# ERN_Main_2.net
KiCad netlist of a schematic drawn in Altium Designer
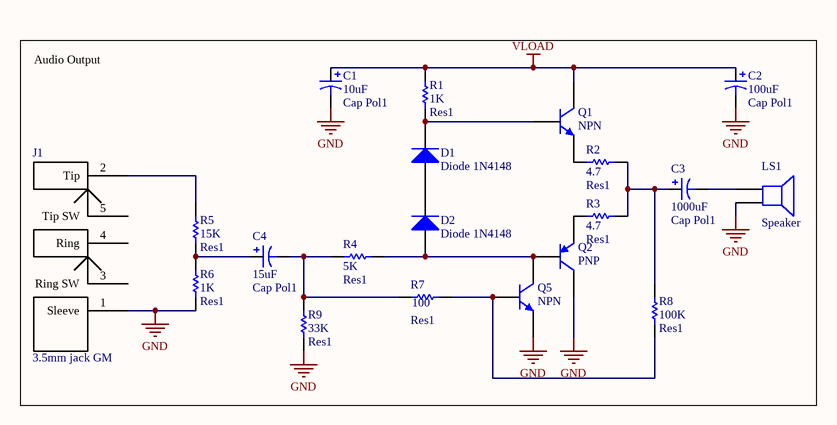
[diagram p0: ERN_Main_2.SchDoc]

(export (version "E")
  (design (tool "Eeschema 10.0.6"))
  (components
    (comp (ref "C1")
      (value "Cap Pol1")
      (footprint "Cap_10uF")
      (description "Polarized Capacitor (Radial)")
      (fields (field (name "ALTIUM_VALUE") "10uF") (field (name "PUBLISHER") "Altium Limited"))
      (libsource (lib "Miscellaneous Devices") (part "Cap Pol1"))
    )
    (comp (ref "C2")
      (value "Cap Pol1")
      (footprint "Cap_47uF_100uF")
      (description "Polarized Capacitor (Radial)")
      (fields (field (name "ALTIUM_VALUE") "100uF") (field (name "PUBLISHER") "Altium Limited"))
      (libsource (lib "Miscellaneous Devices") (part "Cap Pol1"))
    )
    (comp (ref "C3")
      (value "Cap Pol1")
      (footprint "Cap_1000uF")
      (description "Polarized Capacitor (Radial)")
      (fields (field (name "ALTIUM_VALUE") "1000uF") (field (name "PUBLISHER") "Altium Limited"))
      (libsource (lib "Miscellaneous Devices") (part "Cap Pol1"))
    )
    (comp (ref "C4")
      (value "Cap Pol1")
      (footprint "Cap_10uF")
      (description "Polarized Capacitor (Radial)")
      (fields (field (name "ALTIUM_VALUE") "15uF") (field (name "PUBLISHER") "Altium Limited"))
      (libsource (lib "Miscellaneous Devices") (part "Cap Pol1"))
    )
    (comp (ref "D1")
      (value "Diode 1N4148")
      (footprint "DO-35")
      (description "High Conductance Fast Diode")
      (fields (field (name "PUBLISHER") "Altium Limited"))
      (libsource (lib "Miscellaneous Devices") (part "Diode 1N4148"))
    )
    (comp (ref "D2")
      (value "Diode 1N4148")
      (footprint "DO-35")
      (description "High Conductance Fast Diode")
      (fields (field (name "PUBLISHER") "Altium Limited"))
      (libsource (lib "Miscellaneous Devices") (part "Diode 1N4148"))
    )
    (comp (ref "J1")
      (value "3.5mm jack GM")
      (footprint "3.5mm jack GM")
      (libsource (lib "ECE Lib 22") (part "3.5mm jack GM"))
    )
    (comp (ref "LS1")
      (value "Speaker")
      (footprint "PIN2")
      (description "Loudspeaker")
      (fields (field (name "PUBLISHER") "Altium Limited"))
      (libsource (lib "Miscellaneous Devices") (part "Speaker"))
    )
    (comp (ref "Q1")
      (value "NPN")
      (footprint "TO92254P460H750-3")
      (description "NPN Bipolar Transistor")
      (fields (field (name "PUBLISHER") "Altium Limited"))
      (libsource (lib "Miscellaneous Devices") (part "NPN"))
    )
    (comp (ref "Q2")
      (value "PNP")
      (footprint "TO92254P460H750-3")
      (description "PNP Bipolar Transistor")
      (fields (field (name "PUBLISHER") "Altium Limited"))
      (libsource (lib "Miscellaneous Devices") (part "PNP"))
    )
    (comp (ref "Q5")
      (value "NPN")
      (footprint "TO92254P460H750-3")
      (description "NPN Bipolar Transistor")
      (fields (field (name "PUBLISHER") "Altium Limited"))
      (libsource (lib "Miscellaneous Devices") (part "NPN"))
    )
    (comp (ref "R1")
      (value "Res1")
      (footprint "AXIAL-0.3")
      (description "Resistor")
      (fields (field (name "ALTIUM_VALUE") "1K") (field (name "PUBLISHER") "Altium Limited"))
      (libsource (lib "Miscellaneous Devices") (part "Res1"))
    )
    (comp (ref "R2")
      (value "Res1")
      (footprint "AXIAL-0.3")
      (description "Resistor")
      (fields (field (name "ALTIUM_VALUE") "4.7") (field (name "PUBLISHER") "Altium Limited"))
      (libsource (lib "Miscellaneous Devices") (part "Res1"))
    )
    (comp (ref "R3")
      (value "Res1")
      (footprint "AXIAL-0.3")
      (description "Resistor")
      (fields (field (name "ALTIUM_VALUE") "4.7") (field (name "PUBLISHER") "Altium Limited"))
      (libsource (lib "Miscellaneous Devices") (part "Res1"))
    )
    (comp (ref "R4")
      (value "Res1")
      (footprint "AXIAL-0.3")
      (description "Resistor")
      (fields (field (name "ALTIUM_VALUE") "5K") (field (name "PUBLISHER") "Altium Limited"))
      (libsource (lib "Miscellaneous Devices") (part "Res1"))
    )
    (comp (ref "R5")
      (value "Res1")
      (footprint "AXIAL-0.3")
      (description "Resistor")
      (fields (field (name "ALTIUM_VALUE") "15K") (field (name "PUBLISHER") "Altium Limited"))
      (libsource (lib "Miscellaneous Devices") (part "Res1"))
    )
    (comp (ref "R6")
      (value "Res1")
      (footprint "AXIAL-0.3")
      (description "Resistor")
      (fields (field (name "ALTIUM_VALUE") "1K") (field (name "PUBLISHER") "Altium Limited"))
      (libsource (lib "Miscellaneous Devices") (part "Res1"))
    )
    (comp (ref "R7")
      (value "Res1")
      (footprint "AXIAL-0.3")
      (description "Resistor")
      (fields (field (name "ALTIUM_VALUE") "100") (field (name "PUBLISHER") "Altium Limited"))
      (libsource (lib "Miscellaneous Devices") (part "Res1"))
    )
    (comp (ref "R8")
      (value "Res1")
      (footprint "AXIAL-0.3")
      (description "Resistor")
      (fields (field (name "ALTIUM_VALUE") "100K") (field (name "PUBLISHER") "Altium Limited"))
      (libsource (lib "Miscellaneous Devices") (part "Res1"))
    )
    (comp (ref "R9")
      (value "Res1")
      (footprint "AXIAL-0.3")
      (description "Resistor")
      (fields (field (name "ALTIUM_VALUE") "33K") (field (name "PUBLISHER") "Altium Limited"))
      (libsource (lib "Miscellaneous Devices") (part "Res1"))
    )
  )
  (nets
    (net (code "1") (name "GND") (class "Default")
      (node (ref "C1") (pin "2") (pinfunction "2_2") (pintype "passive"))
      (node (ref "C2") (pin "2") (pinfunction "2_2") (pintype "passive"))
      (node (ref "J1") (pin "1") (pinfunction "Sleeve_1") (pintype "passive"))
      (node (ref "LS1") (pin "2") (pinfunction "2_2") (pintype "passive"))
      (node (ref "Q2") (pin "1") (pinfunction "C_1") (pintype "passive"))
      (node (ref "Q5") (pin "3") (pinfunction "E_3") (pintype "passive"))
      (node (ref "R6") (pin "1") (pinfunction "1_1") (pintype "passive"))
      (node (ref "R9") (pin "1") (pinfunction "1_1") (pintype "passive"))
    )
    (net (code "2") (name "Net-(C3-Pad1)") (class "Default")
      (node (ref "C3") (pin "1") (pinfunction "1_1") (pintype "passive"))
      (node (ref "R2") (pin "2") (pinfunction "2_2") (pintype "passive"))
      (node (ref "R3") (pin "2") (pinfunction "2_2") (pintype "passive"))
      (node (ref "R8") (pin "2") (pinfunction "2_2") (pintype "passive"))
    )
    (net (code "3") (name "Net-(C3-Pad2)") (class "Default")
      (node (ref "C3") (pin "2") (pinfunction "2_2") (pintype "passive"))
      (node (ref "LS1") (pin "1") (pinfunction "1_1") (pintype "passive"))
    )
    (net (code "4") (name "Net-(C4-Pad1)") (class "Default")
      (node (ref "C4") (pin "1") (pinfunction "1_1") (pintype "passive"))
      (node (ref "R5") (pin "1") (pinfunction "1_1") (pintype "passive"))
      (node (ref "R6") (pin "2") (pinfunction "2_2") (pintype "passive"))
    )
    (net (code "5") (name "Net-(C4-Pad2)") (class "Default")
      (node (ref "C4") (pin "2") (pinfunction "2_2") (pintype "passive"))
      (node (ref "R4") (pin "1") (pinfunction "1_1") (pintype "passive"))
      (node (ref "R7") (pin "1") (pinfunction "1_1") (pintype "passive"))
      (node (ref "R9") (pin "2") (pinfunction "2_2") (pintype "passive"))
    )
    (net (code "6") (name "Net-(D1-A)") (class "Default")
      (node (ref "D1") (pin "1") (pinfunction "A_1") (pintype "passive"))
      (node (ref "D2") (pin "2") (pinfunction "K_2") (pintype "passive"))
    )
    (net (code "7") (name "Net-(D1-K)") (class "Default")
      (node (ref "D1") (pin "2") (pinfunction "K_2") (pintype "passive"))
      (node (ref "Q1") (pin "2") (pinfunction "B_2") (pintype "passive"))
      (node (ref "R1") (pin "1") (pinfunction "1_1") (pintype "passive"))
    )
    (net (code "8") (name "Net-(D2-A)") (class "Default")
      (node (ref "D2") (pin "1") (pinfunction "A_1") (pintype "passive"))
      (node (ref "Q2") (pin "2") (pinfunction "B_2") (pintype "passive"))
      (node (ref "Q5") (pin "1") (pinfunction "C_1") (pintype "passive"))
      (node (ref "R4") (pin "2") (pinfunction "2_2") (pintype "passive"))
    )
    (net (code "9") (name "Net-(J1-Tip)") (class "Default")
      (node (ref "J1") (pin "2") (pinfunction "Tip_2") (pintype "passive"))
      (node (ref "R5") (pin "2") (pinfunction "2_2") (pintype "passive"))
    )
    (net (code "10") (name "Net-(Q1-E)") (class "Default")
      (node (ref "Q1") (pin "3") (pinfunction "E_3") (pintype "passive"))
      (node (ref "R2") (pin "1") (pinfunction "1_1") (pintype "passive"))
    )
    (net (code "11") (name "Net-(Q2-E)") (class "Default")
      (node (ref "Q2") (pin "3") (pinfunction "E_3") (pintype "passive"))
      (node (ref "R3") (pin "1") (pinfunction "1_1") (pintype "passive"))
    )
    (net (code "12") (name "Net-(Q5-B)") (class "Default")
      (node (ref "Q5") (pin "2") (pinfunction "B_2") (pintype "passive"))
      (node (ref "R7") (pin "2") (pinfunction "2_2") (pintype "passive"))
      (node (ref "R8") (pin "1") (pinfunction "1_1") (pintype "passive"))
    )
    (net (code "13") (name "VLOAD") (class "Default")
      (node (ref "C1") (pin "1") (pinfunction "1_1") (pintype "passive"))
      (node (ref "C2") (pin "1") (pinfunction "1_1") (pintype "passive"))
      (node (ref "Q1") (pin "1") (pinfunction "C_1") (pintype "passive"))
      (node (ref "R1") (pin "2") (pinfunction "2_2") (pintype "passive"))
    )
    (net (code "14") (name "unconnected-(J1-Ring-Pad4)") (class "Default")
      (node (ref "J1") (pin "4") (pinfunction "Ring_4") (pintype "passive"))
    )
    (net (code "15") (name "unconnected-(J1-Ring_SW-Pad3)") (class "Default")
      (node (ref "J1") (pin "3") (pinfunction "Ring_SW_3") (pintype "passive"))
    )
    (net (code "16") (name "unconnected-(J1-Tip_SW-Pad5)") (class "Default")
      (node (ref "J1") (pin "5") (pinfunction "Tip_SW_5") (pintype "passive"))
    )
  )
)
